# LKS_EVB_MCU072_V1_0.net
KiCad netlist of a schematic drawn in Altium Designer
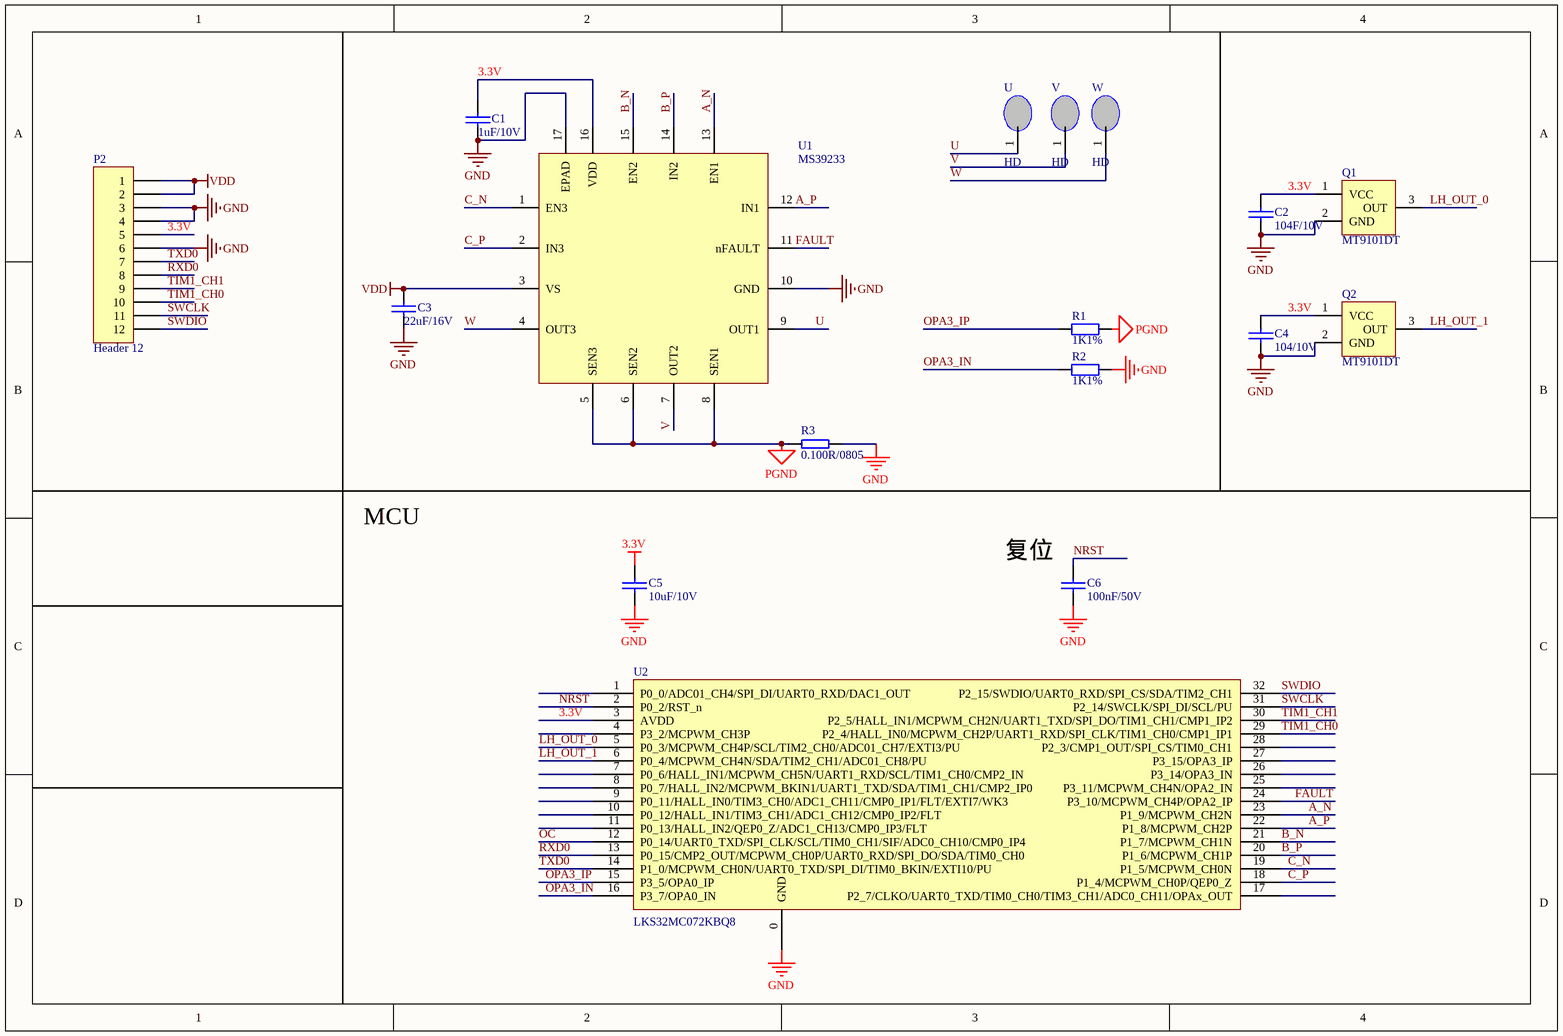
[diagram p0: LKS_EVB_MCU072_V1.0.SchDoc]

(export (version "E")
  (design (tool "Eeschema 10.0.6"))
  (components
    (comp (ref "C1")
      (value "1uF/10V")
      (footprint "C 0402_M")
      (description "Capacitor")
      (libsource (lib "*") (part "C"))
    )
    (comp (ref "C2")
      (value "104F/10V")
      (footprint "C 0402_M")
      (description "Capacitor")
      (libsource (lib "*") (part "C"))
    )
    (comp (ref "C3")
      (value "22uF/16V")
      (footprint "C 0805_M")
      (description "Capacitor")
      (libsource (lib "*") (part "C"))
    )
    (comp (ref "C4")
      (value "104/10V")
      (footprint "C 0402_M")
      (description "Capacitor")
      (libsource (lib "*") (part "C"))
    )
    (comp (ref "C5")
      (value "10uF/10V")
      (footprint "C 0402_M")
      (description "Capacitor")
      (libsource (lib "*") (part "C"))
    )
    (comp (ref "C6")
      (value "100nF/50V")
      (footprint "C 0402_M")
      (description "Capacitor")
      (libsource (lib "*") (part "C"))
    )
    (comp (ref "P2")
      (value "Header 12")
      (footprint "SMD-12")
      (description "Header, 12-Pin")
      (fields (field (name "PUBLISHER") "Altium Limited"))
      (libsource (lib "Miscellaneous Connectors") (part "Header 12"))
    )
    (comp (ref "Q1") (value "MT9101DT") (footprint "DFN1616") (libsource (lib "Schlib1") (part "MT9101DT")))
    (comp (ref "Q2") (value "MT9101DT") (footprint "DFN1616") (libsource (lib "Schlib1") (part "MT9101DT")))
    (comp (ref "R1")
      (value "1K1%")
      (footprint "R 0402_M")
      (description "Resistor")
      (fields (field (name "PUBLISHER") "Altium Limited"))
      (libsource (lib "LINKO_V1.0") (part "Res"))
    )
    (comp (ref "R2")
      (value "1K1%")
      (footprint "R 0402_M")
      (description "Resistor")
      (fields (field (name "PUBLISHER") "Altium Limited"))
      (libsource (lib "LINKO_V1.0") (part "Res"))
    )
    (comp (ref "R3") (value "0.100R/0805") (footprint "R 0805_M") (libsource (lib "*") (part "RES2短")))
    (comp (ref "U") (value "HD") (footprint "HD") (libsource (lib "Schlib1") (part "HD")))
    (comp (ref "U1") (value "MS39233") (footprint "QFN16") (libsource (lib "Schlib1") (part "MS39233")))
    (comp (ref "U2")
      (value "LKS32MC072KBQ8")
      (footprint "QFN32 5x5_M")
      (description "LKS32MC072KBQ8\r\n凌鸥创芯，128KFlash，12KRAM")
      (libsource (lib "LINKO_V1.1") (part "LKS32MC072KBQ82"))
    )
    (comp (ref "V") (value "HD") (footprint "HD") (libsource (lib "Schlib1") (part "HD")))
    (comp (ref "W") (value "HD") (footprint "HD") (libsource (lib "Schlib1") (part "HD")))
  )
  (nets
    (net (code "1") (name "/A_N") (class "Default")
      (node (ref "U1") (pin "13") (pinfunction "EN1_13") (pintype "passive"))
      (node (ref "U2") (pin "23") (pinfunction "P1_9/MCPWM_CH2N_23") (pintype "passive"))
    )
    (net (code "2") (name "/A_P") (class "Default")
      (node (ref "U1") (pin "12") (pinfunction "IN1_12") (pintype "passive"))
      (node (ref "U2") (pin "22") (pinfunction "P1_8/MCPWM_CH2P_22") (pintype "passive"))
    )
    (net (code "3") (name "/B_N") (class "Default")
      (node (ref "U1") (pin "15") (pinfunction "EN2_15") (pintype "passive"))
      (node (ref "U2") (pin "21") (pinfunction "P1_7/MCPWM_CH1N_21") (pintype "passive"))
    )
    (net (code "4") (name "/B_P") (class "Default")
      (node (ref "U1") (pin "14") (pinfunction "IN2_14") (pintype "passive"))
      (node (ref "U2") (pin "20") (pinfunction "P1_6/MCPWM_CH1P_20") (pintype "passive"))
    )
    (net (code "5") (name "/C_N") (class "Default")
      (node (ref "U1") (pin "1") (pinfunction "EN3_1") (pintype "passive"))
      (node (ref "U2") (pin "19") (pinfunction "P1_5/MCPWM_CH0N_19") (pintype "passive"))
    )
    (net (code "6") (name "/C_P") (class "Default")
      (node (ref "U1") (pin "2") (pinfunction "IN3_2") (pintype "passive"))
      (node (ref "U2") (pin "18") (pinfunction "P1_4/MCPWM_CH0P/QEP0_Z_18") (pintype "passive"))
    )
    (net (code "7") (name "/FAULT") (class "Default")
      (node (ref "U1") (pin "11") (pinfunction "nFAULT_11") (pintype "passive"))
      (node (ref "U2") (pin "24") (pinfunction "P3_10/MCPWM_CH4P/OPA2_IP_24") (pintype "passive"))
    )
    (net (code "8") (name "/LH_OUT_0") (class "Default")
      (node (ref "Q1") (pin "3") (pinfunction "OUT_3") (pintype "passive"))
      (node (ref "U2") (pin "5") (pinfunction "P0_3/MCPWM_CH4P/SCL/TIM2_CH0/ADC01_CH7/EXTI3/PU_5") (pintype "passive"))
    )
    (net (code "9") (name "/LH_OUT_1") (class "Default")
      (node (ref "Q2") (pin "3") (pinfunction "OUT_3") (pintype "passive"))
      (node (ref "U2") (pin "6") (pinfunction "P0_4/MCPWM_CH4N/SDA/TIM2_CH1/ADC01_CH8/PU_6") (pintype "passive"))
    )
    (net (code "10") (name "/NRST") (class "Default")
      (node (ref "C6") (pin "1") (pinfunction "1_1") (pintype "passive"))
      (node (ref "U2") (pin "2") (pinfunction "P0_2/RST_n_2") (pintype "passive"))
    )
    (net (code "11") (name "/OC") (class "Default")
      (node (ref "U2") (pin "12") (pinfunction "P0_14/UART0_TXD/SPI_CLK/SCL/TIM0_CH1/SIF/ADC0_CH10/CMP0_IP4_12") (pintype "passive"))
    )
    (net (code "12") (name "/OPA3_IN") (class "Default")
      (node (ref "R2") (pin "2") (pinfunction "2_2") (pintype "passive"))
      (node (ref "U2") (pin "16") (pinfunction "P3_7/OPA0_IN_16") (pintype "passive"))
    )
    (net (code "13") (name "/OPA3_IP") (class "Default")
      (node (ref "R1") (pin "2") (pinfunction "2_2") (pintype "passive"))
      (node (ref "U2") (pin "15") (pinfunction "P3_5/OPA0_IP_15") (pintype "passive"))
    )
    (net (code "14") (name "/RXD0") (class "Default")
      (node (ref "P2") (pin "8") (pinfunction "8_8") (pintype "passive"))
      (node (ref "U2") (pin "13") (pinfunction "P0_15/CMP2_OUT/MCPWM_CH0P/UART0_RXD/SPI_DO/SDA/TIM0_CH0_13") (pintype "passive"))
    )
    (net (code "15") (name "/SWCLK") (class "Default")
      (node (ref "P2") (pin "11") (pinfunction "11_11") (pintype "passive"))
      (node (ref "U2") (pin "31") (pinfunction "P2_14/SWCLK/SPI_DI/SCL/PU_31") (pintype "passive"))
    )
    (net (code "16") (name "/SWDIO") (class "Default")
      (node (ref "P2") (pin "12") (pinfunction "12_12") (pintype "passive"))
      (node (ref "U2") (pin "32") (pinfunction "P2_15/SWDIO/UART0_RXD/SPI_CS/SDA/TIM2_CH1_32") (pintype "passive"))
    )
    (net (code "17") (name "/TIM1_CH0") (class "Default")
      (node (ref "P2") (pin "10") (pinfunction "10_10") (pintype "passive"))
      (node (ref "U2") (pin "29") (pinfunction "P2_4/HALL_IN0/MCPWM_CH2P/UART1_RXD/SPI_CLK/TIM1_CH0/CMP1_IP1_29") (pintype "passive"))
    )
    (net (code "18") (name "/TIM1_CH1") (class "Default")
      (node (ref "P2") (pin "9") (pinfunction "9_9") (pintype "passive"))
      (node (ref "U2") (pin "30") (pinfunction "P2_5/HALL_IN1/MCPWM_CH2N/UART1_TXD/SPI_DO/TIM1_CH1/CMP1_IP2_30") (pintype "passive"))
    )
    (net (code "19") (name "/TXD0") (class "Default")
      (node (ref "P2") (pin "7") (pinfunction "7_7") (pintype "passive"))
      (node (ref "U2") (pin "14") (pinfunction "P1_0/MCPWM_CH0N/UART0_TXD/SPI_DI/TIM0_BKIN/EXTI10/PU_14") (pintype "passive"))
    )
    (net (code "20") (name "/U") (class "Default")
      (node (ref "U") (pin "1") (pinfunction "1_1") (pintype "passive"))
      (node (ref "U1") (pin "9") (pinfunction "OUT1_9") (pintype "passive"))
    )
    (net (code "21") (name "/V") (class "Default")
      (node (ref "U1") (pin "7") (pinfunction "OUT2_7") (pintype "passive"))
      (node (ref "V") (pin "1") (pinfunction "1_1") (pintype "passive"))
    )
    (net (code "22") (name "/W") (class "Default")
      (node (ref "U1") (pin "4") (pinfunction "OUT3_4") (pintype "passive"))
      (node (ref "W") (pin "1") (pinfunction "1_1") (pintype "passive"))
    )
    (net (code "23") (name "3.3V") (class "Default")
      (node (ref "C1") (pin "2") (pinfunction "2_2") (pintype "passive"))
      (node (ref "C2") (pin "2") (pinfunction "2_2") (pintype "passive"))
      (node (ref "C4") (pin "2") (pinfunction "2_2") (pintype "passive"))
      (node (ref "C5") (pin "2") (pinfunction "2_2") (pintype "passive"))
      (node (ref "P2") (pin "5") (pinfunction "5_5") (pintype "passive"))
      (node (ref "Q1") (pin "1") (pinfunction "VCC_1") (pintype "passive"))
      (node (ref "Q2") (pin "1") (pinfunction "VCC_1") (pintype "passive"))
      (node (ref "U1") (pin "16") (pinfunction "VDD_16") (pintype "passive"))
      (node (ref "U2") (pin "3") (pinfunction "AVDD_3") (pintype "passive"))
    )
    (net (code "24") (name "GND") (class "Default")
      (node (ref "C1") (pin "1") (pinfunction "1_1") (pintype "passive"))
      (node (ref "C2") (pin "1") (pinfunction "1_1") (pintype "passive"))
      (node (ref "C3") (pin "1") (pinfunction "1_1") (pintype "passive"))
      (node (ref "C4") (pin "1") (pinfunction "1_1") (pintype "passive"))
      (node (ref "C5") (pin "1") (pinfunction "1_1") (pintype "passive"))
      (node (ref "C6") (pin "2") (pinfunction "2_2") (pintype "passive"))
      (node (ref "P2") (pin "3") (pinfunction "3_3") (pintype "passive"))
      (node (ref "P2") (pin "4") (pinfunction "4_4") (pintype "passive"))
      (node (ref "P2") (pin "6") (pinfunction "6_6") (pintype "passive"))
      (node (ref "Q1") (pin "2") (pinfunction "GND_2") (pintype "passive"))
      (node (ref "Q2") (pin "2") (pinfunction "GND_2") (pintype "passive"))
      (node (ref "R2") (pin "1") (pinfunction "1_1") (pintype "passive"))
      (node (ref "R3") (pin "2") (pinfunction "2_2") (pintype "passive"))
      (node (ref "U1") (pin "10") (pinfunction "GND_10") (pintype "passive"))
      (node (ref "U1") (pin "17") (pinfunction "EPAD_17") (pintype "passive"))
      (node (ref "U2") (pin "0") (pinfunction "GND_0") (pintype "passive"))
    )
    (net (code "25") (name "PGND") (class "Default")
      (node (ref "R1") (pin "1") (pinfunction "1_1") (pintype "passive"))
      (node (ref "R3") (pin "1") (pinfunction "1_1") (pintype "passive"))
      (node (ref "U1") (pin "5") (pinfunction "SEN3_5") (pintype "passive"))
      (node (ref "U1") (pin "6") (pinfunction "SEN2_6") (pintype "passive"))
      (node (ref "U1") (pin "8") (pinfunction "SEN1_8") (pintype "passive"))
    )
    (net (code "26") (name "VDD") (class "Default")
      (node (ref "C3") (pin "2") (pinfunction "2_2") (pintype "passive"))
      (node (ref "P2") (pin "1") (pinfunction "1_1") (pintype "passive"))
      (node (ref "P2") (pin "2") (pinfunction "2_2") (pintype "passive"))
      (node (ref "U1") (pin "3") (pinfunction "VS_3") (pintype "passive"))
    )
    (net (code "27") (name "unconnected-(U2-P0_0{slash}ADC01_CH4{slash}SPI_DI{slash}UART0_RXD{slash}DAC1_OUT-Pad1)") (class "Default")
      (node (ref "U2") (pin "1") (pinfunction "P0_0/ADC01_CH4/SPI_DI/UART0_RXD/DAC1_OUT_1") (pintype "passive"))
    )
    (net (code "28") (name "unconnected-(U2-P0_6{slash}HALL_IN1{slash}MCPWM_CH5N{slash}UART1_RXD{slash}SCL{slash}TIM1_CH0{slash}CMP2_IN-Pad7)") (class "Default")
      (node (ref "U2") (pin "7") (pinfunction "P0_6/HALL_IN1/MCPWM_CH5N/UART1_RXD/SCL/TIM1_CH0/CMP2_IN_7") (pintype "passive"))
    )
    (net (code "29") (name "unconnected-(U2-P0_7{slash}HALL_IN2{slash}MCPWM_BKIN1{slash}UART1_TXD{slash}SDA{slash}TIM1_CH1{slash}CMP2_IP0-Pad8)") (class "Default")
      (node (ref "U2") (pin "8") (pinfunction "P0_7/HALL_IN2/MCPWM_BKIN1/UART1_TXD/SDA/TIM1_CH1/CMP2_IP0_8") (pintype "passive"))
    )
    (net (code "30") (name "unconnected-(U2-P0_11{slash}HALL_IN0{slash}TIM3_CH0{slash}ADC1_CH11{slash}CMP0_IP1{slash}FLT{slash}EXTI7{slash}WK3-Pad9)") (class "Default")
      (node (ref "U2") (pin "9") (pinfunction "P0_11/HALL_IN0/TIM3_CH0/ADC1_CH11/CMP0_IP1/FLT/EXTI7/WK3_9") (pintype "passive"))
    )
    (net (code "31") (name "unconnected-(U2-P0_12{slash}HALL_IN1{slash}TIM3_CH1{slash}ADC1_CH12{slash}CMP0_IP2{slash}FLT-Pad10)") (class "Default")
      (node (ref "U2") (pin "10") (pinfunction "P0_12/HALL_IN1/TIM3_CH1/ADC1_CH12/CMP0_IP2/FLT_10") (pintype "passive"))
    )
    (net (code "32") (name "unconnected-(U2-P0_13{slash}HALL_IN2{slash}QEP0_Z{slash}ADC1_CH13{slash}CMP0_IP3{slash}FLT-Pad11)") (class "Default")
      (node (ref "U2") (pin "11") (pinfunction "P0_13/HALL_IN2/QEP0_Z/ADC1_CH13/CMP0_IP3/FLT_11") (pintype "passive"))
    )
    (net (code "33") (name "unconnected-(U2-P2_3{slash}CMP1_OUT{slash}SPI_CS{slash}TIM0_CH1-Pad28)") (class "Default")
      (node (ref "U2") (pin "28") (pinfunction "P2_3/CMP1_OUT/SPI_CS/TIM0_CH1_28") (pintype "passive"))
    )
    (net (code "34") (name "unconnected-(U2-P2_7{slash}CLKO{slash}UART0_TXD{slash}TIM0_CH0{slash}TIM3_CH1{slash}ADC0_CH11{slash}OPAx_OUT-Pad17)") (class "Default")
      (node (ref "U2") (pin "17") (pinfunction "P2_7/CLKO/UART0_TXD/TIM0_CH0/TIM3_CH1/ADC0_CH11/OPAx_OUT_17") (pintype "passive"))
    )
    (net (code "35") (name "unconnected-(U2-P3_2{slash}MCPWM_CH3P-Pad4)") (class "Default")
      (node (ref "U2") (pin "4") (pinfunction "P3_2/MCPWM_CH3P_4") (pintype "passive"))
    )
    (net (code "36") (name "unconnected-(U2-P3_11{slash}MCPWM_CH4N{slash}OPA2_IN-Pad25)") (class "Default")
      (node (ref "U2") (pin "25") (pinfunction "P3_11/MCPWM_CH4N/OPA2_IN_25") (pintype "passive"))
    )
    (net (code "37") (name "unconnected-(U2-P3_14{slash}OPA3_IN-Pad26)") (class "Default")
      (node (ref "U2") (pin "26") (pinfunction "P3_14/OPA3_IN_26") (pintype "passive"))
    )
    (net (code "38") (name "unconnected-(U2-P3_15{slash}OPA3_IP-Pad27)") (class "Default")
      (node (ref "U2") (pin "27") (pinfunction "P3_15/OPA3_IP_27") (pintype "passive"))
    )
  )
)
